# 21FX_revd_power.net
KiCad netlist of a schematic drawn in Altium Designer
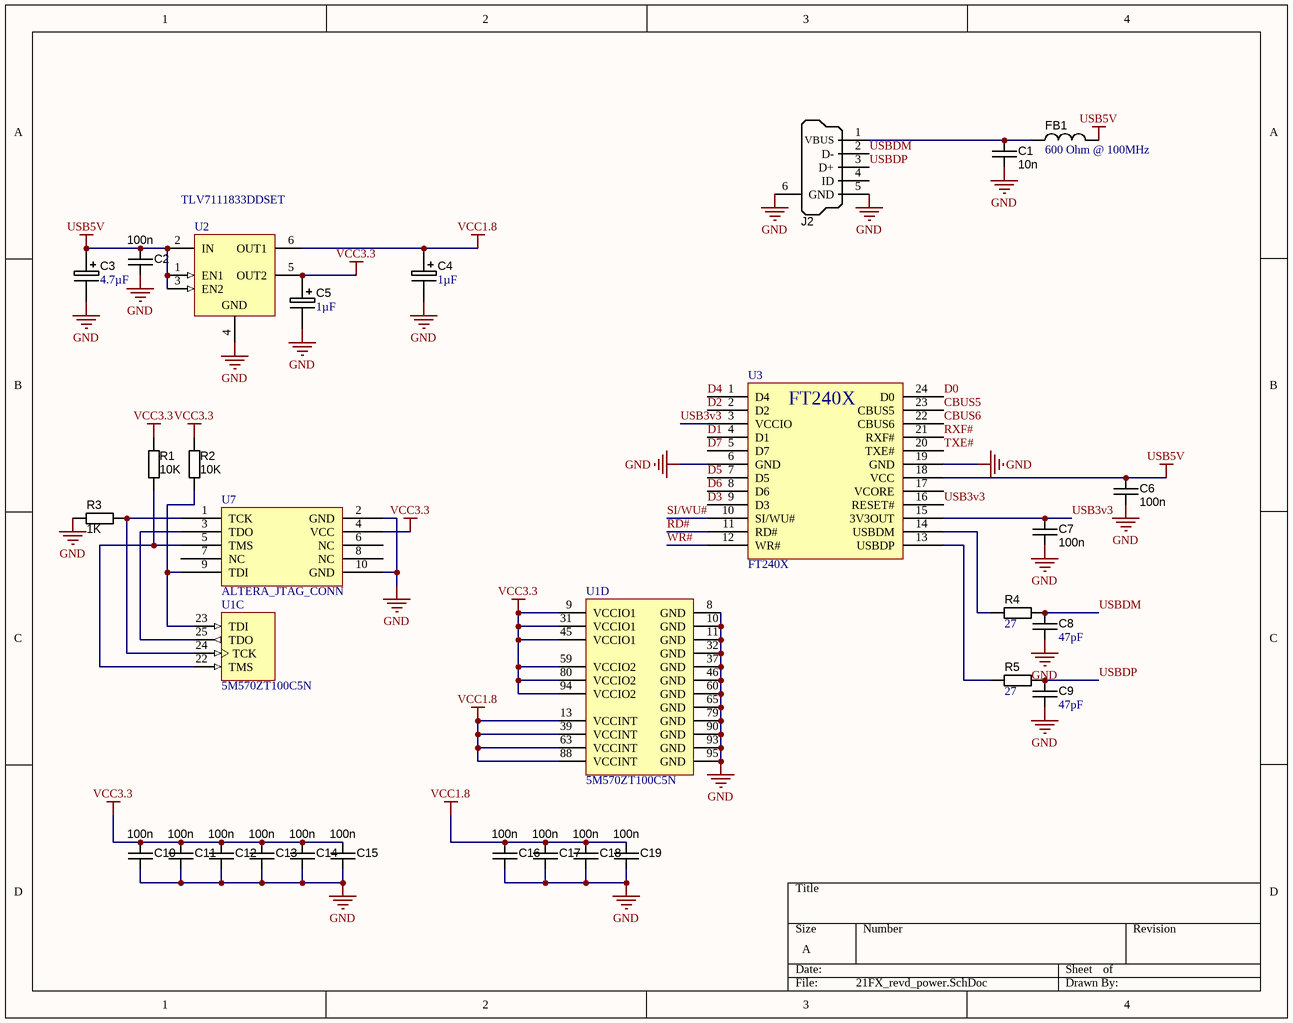
[diagram p0: 21FX_revd_power.SchDoc]

(export (version "E")
  (design (tool "Eeschema 10.0.6"))
  (components
    (comp (ref "C1")
      (value "10n")
      (footprint "CAPC1608X90N")
      (description "Capacitor SMD Cer 10nF 10% 50V X7R 0603")
      (fields (field (name "TOLERANCE") "±10%") (field (name "Comment") "approved sub OK"))
      (libsource (lib "snes_hook_parts") (part "CAPC_10n_0603_X7R_50V_10%"))
    )
    (comp (ref "C2")
      (value "100n")
      (footprint "CAPC1608X90N")
      (description "Capacitor SMD Cer 100nF 10% 50V X7R 0603")
      (fields (field (name "TOLERANCE") "±10%") (field (name "Comment") "approved sub OK"))
      (libsource (lib "snes_hook_parts") (part "CAPC_100n_0603_X7R_50V_10%"))
    )
    (comp (ref "C3")
      (value "~")
      (footprint "CAPC1608X90N")
      (description "Capacitor SMD 4.7uF 10% 10V")
      (fields
        (field (name "MANUFACTURER") "Yageo")
        (field (name "MANUFACTURER PART NUMBER") "CC0603KRX5R6BB475")
        (field (name "CAPACITANCE") "4.7µF")
      )
      (libsource (lib "snes_hook_parts") (part "CAPT_4_7u_0603_10V"))
    )
    (comp (ref "C4")
      (value "~")
      (footprint "CAPC1608X90N")
      (description "Capacitor SMD 1uF 10% 10V")
      (fields
        (field (name "MANUFACTURER") "Murata Electronics North America")
        (field (name "MANUFACTURER PART NUMBER") "GRM155R61A105KE15D")
        (field (name "CAPACITANCE") "1µF")
      )
      (libsource (lib "snes_hook_parts") (part "CAPT_1u_0603_10V"))
    )
    (comp (ref "C5")
      (value "~")
      (footprint "CAPC1608X90N")
      (description "Capacitor SMD 1uF 10% 10V")
      (fields
        (field (name "MANUFACTURER") "Murata Electronics North America")
        (field (name "MANUFACTURER PART NUMBER") "GRM155R61A105KE15D")
        (field (name "CAPACITANCE") "1µF")
      )
      (libsource (lib "snes_hook_parts") (part "CAPT_1u_0603_10V"))
    )
    (comp (ref "C6")
      (value "100n")
      (footprint "CAPC1608X90N")
      (description "Capacitor SMD Cer 100nF 10% 50V X7R 0603")
      (fields (field (name "TOLERANCE") "±10%") (field (name "Comment") "approved sub OK"))
      (libsource (lib "snes_hook_parts") (part "CAPC_100n_0603_X7R_50V_10%"))
    )
    (comp (ref "C7")
      (value "100n")
      (footprint "CAPC1608X90N")
      (description "Capacitor SMD Cer 100nF 10% 50V X7R 0603")
      (fields (field (name "TOLERANCE") "±10%") (field (name "Comment") "approved sub OK"))
      (libsource (lib "snes_hook_parts") (part "CAPC_100n_0603_X7R_50V_10%"))
    )
    (comp (ref "C8")
      (value "~")
      (footprint "CAPC1608X90N")
      (description "Capacitor SMD Cer 47pF 5% 50V X7R 0603")
      (fields (field (name "TOLERANCE") "±5%") (field (name "CAPACITANCE") "47pF"))
      (libsource (lib "snes_hook_parts") (part "CAPC_47p_0603_X7R_50V_5%"))
    )
    (comp (ref "C9")
      (value "~")
      (footprint "CAPC1608X90N")
      (description "Capacitor SMD Cer 47pF 5% 50V X7R 0603")
      (fields (field (name "TOLERANCE") "±5%") (field (name "CAPACITANCE") "47pF"))
      (libsource (lib "snes_hook_parts") (part "CAPC_47p_0603_X7R_50V_5%"))
    )
    (comp (ref "C10")
      (value "100n")
      (footprint "CAPC1608X90N")
      (description "Capacitor SMD Cer 100nF 10% 50V X7R 0603")
      (fields (field (name "TOLERANCE") "±10%") (field (name "Comment") "approved sub OK"))
      (libsource (lib "snes_hook_parts") (part "CAPC_100n_0603_X7R_50V_10%"))
    )
    (comp (ref "C11")
      (value "100n")
      (footprint "CAPC1608X90N")
      (description "Capacitor SMD Cer 100nF 10% 50V X7R 0603")
      (fields (field (name "TOLERANCE") "±10%") (field (name "Comment") "approved sub OK"))
      (libsource (lib "snes_hook_parts") (part "CAPC_100n_0603_X7R_50V_10%"))
    )
    (comp (ref "C12")
      (value "100n")
      (footprint "CAPC1608X90N")
      (description "Capacitor SMD Cer 100nF 10% 50V X7R 0603")
      (fields (field (name "TOLERANCE") "±10%") (field (name "Comment") "approved sub OK"))
      (libsource (lib "snes_hook_parts") (part "CAPC_100n_0603_X7R_50V_10%"))
    )
    (comp (ref "C13")
      (value "100n")
      (footprint "CAPC1608X90N")
      (description "Capacitor SMD Cer 100nF 10% 50V X7R 0603")
      (fields (field (name "TOLERANCE") "±10%") (field (name "Comment") "approved sub OK"))
      (libsource (lib "snes_hook_parts") (part "CAPC_100n_0603_X7R_50V_10%"))
    )
    (comp (ref "C14")
      (value "100n")
      (footprint "CAPC1608X90N")
      (description "Capacitor SMD Cer 100nF 10% 50V X7R 0603")
      (fields (field (name "TOLERANCE") "±10%") (field (name "Comment") "approved sub OK"))
      (libsource (lib "snes_hook_parts") (part "CAPC_100n_0603_X7R_50V_10%"))
    )
    (comp (ref "C15")
      (value "100n")
      (footprint "CAPC1608X90N")
      (description "Capacitor SMD Cer 100nF 10% 50V X7R 0603")
      (fields (field (name "TOLERANCE") "±10%") (field (name "Comment") "approved sub OK"))
      (libsource (lib "snes_hook_parts") (part "CAPC_100n_0603_X7R_50V_10%"))
    )
    (comp (ref "C16")
      (value "100n")
      (footprint "CAPC1608X90N")
      (description "Capacitor SMD Cer 100nF 10% 50V X7R 0603")
      (fields (field (name "TOLERANCE") "±10%") (field (name "Comment") "approved sub OK"))
      (libsource (lib "snes_hook_parts") (part "CAPC_100n_0603_X7R_50V_10%"))
    )
    (comp (ref "C17")
      (value "100n")
      (footprint "CAPC1608X90N")
      (description "Capacitor SMD Cer 100nF 10% 50V X7R 0603")
      (fields (field (name "TOLERANCE") "±10%") (field (name "Comment") "approved sub OK"))
      (libsource (lib "snes_hook_parts") (part "CAPC_100n_0603_X7R_50V_10%"))
    )
    (comp (ref "C18")
      (value "100n")
      (footprint "CAPC1608X90N")
      (description "Capacitor SMD Cer 100nF 10% 50V X7R 0603")
      (fields (field (name "TOLERANCE") "±10%") (field (name "Comment") "approved sub OK"))
      (libsource (lib "snes_hook_parts") (part "CAPC_100n_0603_X7R_50V_10%"))
    )
    (comp (ref "C19")
      (value "100n")
      (footprint "CAPC1608X90N")
      (description "Capacitor SMD Cer 100nF 10% 50V X7R 0603")
      (fields (field (name "TOLERANCE") "±10%") (field (name "Comment") "approved sub OK"))
      (libsource (lib "snes_hook_parts") (part "CAPC_100n_0603_X7R_50V_10%"))
    )
    (comp (ref "FB1")
      (value "~")
      (footprint "FBC2012N")
      (description "Ferrite bead 600 Ohm at 100 MHz 1.5A 0805 SMD")
      (fields (field (name "IMPEDANCE @ FREQUENCY") "600 Ohm @ 100MHz"))
      (libsource (lib "snes_hook_parts") (part "FERRITE_600-100MHz_0805"))
    )
    (comp (ref "J2")
      (value "USB_Mini-B_TH")
      (footprint "USB_MINI-B_WURTH-TH")
      (description "Connector TH USB Type Mini-B")
      (fields
        (field (name "MANUFACTURER") "Wurth Electronics Inc")
        (field (name "MANUFACTURER PART NUMBER") "651005136521")
      )
      (libsource (lib "snes_hook_parts") (part "USB_Mini-B_TH"))
    )
    (comp (ref "R1")
      (value "10K")
      (footprint "RESC1608X55N")
      (description "Resistor SMD chip 10k Ohm 0.1W 5% 0603")
      (fields (field (name "TOLERANCE") "±5%") (field (name "Comment") "Thick Film"))
      (libsource (lib "snes_hook_parts") (part "RES_10K_0603_5%"))
    )
    (comp (ref "R2")
      (value "10K")
      (footprint "RESC1608X55N")
      (description "Resistor SMD chip 10k Ohm 0.1W 5% 0603")
      (fields (field (name "TOLERANCE") "±5%") (field (name "Comment") "Thick Film"))
      (libsource (lib "snes_hook_parts") (part "RES_10K_0603_5%"))
    )
    (comp (ref "R3")
      (value "1K")
      (footprint "RESC1608X55N")
      (description "Resistor SMD chip 1k Ohm 0.1W 5% 0603")
      (fields (field (name "TOLERANCE") "±5%") (field (name "Comment") "Thick Film"))
      (libsource (lib "snes_hook_parts") (part "RES_1K_0603_5%"))
    )
    (comp (ref "R4")
      (value "Thick Film")
      (footprint "RESC1608X55N")
      (description "Resistor SMD chip 27 Ohm 0.1W 5% 0603")
      (fields (field (name "TOLERANCE") "±5%") (field (name "RESISTANCE (OHMS)") "27"))
      (libsource (lib "snes_hook_parts") (part "RES_27R_0603_5%"))
    )
    (comp (ref "R5")
      (value "Thick Film")
      (footprint "RESC1608X55N")
      (description "Resistor SMD chip 27 Ohm 0.1W 5% 0603")
      (fields (field (name "TOLERANCE") "±5%") (field (name "RESISTANCE (OHMS)") "27"))
      (libsource (lib "snes_hook_parts") (part "RES_27R_0603_5%"))
    )
    (comp (ref "U1")
      (value "5M570ZT100C5N")
      (footprint "TQFP100_A-120_N")
      (libsource (lib "snes_hook_parts") (part "5M570ZT100C5N"))
    )
    (comp (ref "U2")
      (value "TLV7111833DDSET")
      (footprint "TI-DSE6_V")
      (fields (field (name "MANUFACTURER") "Texas Instruments"))
      (libsource (lib "TI Power Management Linear Regulator Dual Channel LDO") (part "TLV7111833DDSET"))
    )
    (comp (ref "U3")
      (value "FT240X")
      (footprint "SSOP-24")
      (libsource (lib "snes_hook_parts") (part "FT240X"))
    )
    (comp (ref "U7")
      (value "ALTERA_JTAG_CONN")
      (footprint "JTAG_CONN")
      (libsource (lib "snes_hook_parts") (part "ALTERA_JTAG_CONN"))
    )
  )
  (nets
    (net (code "1") (name "/CBUS5") (class "Default")
      (node (ref "U3") (pin "23") (pinfunction "CBUS5_23") (pintype "passive"))
    )
    (net (code "2") (name "/CBUS6") (class "Default")
      (node (ref "U3") (pin "22") (pinfunction "CBUS6_22") (pintype "passive"))
    )
    (net (code "3") (name "/D0") (class "Default")
      (node (ref "U3") (pin "24") (pinfunction "D0_24") (pintype "passive"))
    )
    (net (code "4") (name "/D1") (class "Default")
      (node (ref "U3") (pin "4") (pinfunction "D1_4") (pintype "passive"))
    )
    (net (code "5") (name "/D2") (class "Default")
      (node (ref "U3") (pin "2") (pinfunction "D2_2") (pintype "passive"))
    )
    (net (code "6") (name "/D3") (class "Default")
      (node (ref "U3") (pin "9") (pinfunction "D3_9") (pintype "passive"))
    )
    (net (code "7") (name "/D4") (class "Default")
      (node (ref "U3") (pin "1") (pinfunction "D4_1") (pintype "passive"))
    )
    (net (code "8") (name "/D5") (class "Default")
      (node (ref "U3") (pin "7") (pinfunction "D5_7") (pintype "passive"))
    )
    (net (code "9") (name "/D6") (class "Default")
      (node (ref "U3") (pin "8") (pinfunction "D6_8") (pintype "passive"))
    )
    (net (code "10") (name "/D7") (class "Default")
      (node (ref "U3") (pin "5") (pinfunction "D7_5") (pintype "passive"))
    )
    (net (code "11") (name "/RD#") (class "Default")
      (node (ref "U3") (pin "11") (pinfunction "RD#_11") (pintype "passive"))
    )
    (net (code "12") (name "/RXF#") (class "Default")
      (node (ref "U3") (pin "21") (pinfunction "RXF#_21") (pintype "passive"))
    )
    (net (code "13") (name "/SI{slash}WU#") (class "Default")
      (node (ref "U3") (pin "10") (pinfunction "SI/WU#_10") (pintype "passive"))
    )
    (net (code "14") (name "/TXE#") (class "Default")
      (node (ref "U3") (pin "20") (pinfunction "TXE#_20") (pintype "passive"))
    )
    (net (code "15") (name "/USB3v3") (class "Default")
      (node (ref "C7") (pin "1") (pintype "passive"))
      (node (ref "U3") (pin "15") (pinfunction "3V3OUT_15") (pintype "passive"))
      (node (ref "U3") (pin "16") (pinfunction "RESET#_16") (pintype "passive"))
      (node (ref "U3") (pin "3") (pinfunction "VCCIO_3") (pintype "passive"))
    )
    (net (code "16") (name "/USBDM") (class "Default")
      (node (ref "C8") (pin "1") (pintype "passive"))
      (node (ref "J2") (pin "2") (pinfunction "D-_2") (pintype "passive"))
      (node (ref "R4") (pin "2") (pinfunction "2_2") (pintype "passive"))
    )
    (net (code "17") (name "/USBDP") (class "Default")
      (node (ref "C9") (pin "1") (pintype "passive"))
      (node (ref "J2") (pin "3") (pinfunction "D+_3") (pintype "passive"))
      (node (ref "R5") (pin "2") (pinfunction "2_2") (pintype "passive"))
    )
    (net (code "18") (name "/WR#") (class "Default")
      (node (ref "U3") (pin "12") (pinfunction "WR#_12") (pintype "passive"))
    )
    (net (code "19") (name "GND") (class "Default")
      (node (ref "C1") (pin "2") (pintype "passive"))
      (node (ref "C10") (pin "2") (pintype "passive"))
      (node (ref "C11") (pin "2") (pintype "passive"))
      (node (ref "C12") (pin "2") (pintype "passive"))
      (node (ref "C13") (pin "2") (pintype "passive"))
      (node (ref "C14") (pin "2") (pintype "passive"))
      (node (ref "C15") (pin "2") (pintype "passive"))
      (node (ref "C16") (pin "2") (pintype "passive"))
      (node (ref "C17") (pin "2") (pintype "passive"))
      (node (ref "C18") (pin "2") (pintype "passive"))
      (node (ref "C19") (pin "2") (pintype "passive"))
      (node (ref "C2") (pin "2") (pintype "passive"))
      (node (ref "C3") (pin "2") (pintype "passive"))
      (node (ref "C4") (pin "2") (pintype "passive"))
      (node (ref "C5") (pin "2") (pintype "passive"))
      (node (ref "C6") (pin "2") (pintype "passive"))
      (node (ref "C7") (pin "2") (pintype "passive"))
      (node (ref "C8") (pin "2") (pintype "passive"))
      (node (ref "C9") (pin "2") (pintype "passive"))
      (node (ref "J2") (pin "5") (pinfunction "GND_5") (pintype "passive"))
      (node (ref "J2") (pin "6") (pinfunction "Shell_6") (pintype "passive"))
      (node (ref "R3") (pin "1") (pinfunction "1_1") (pintype "passive"))
      (node (ref "U1") (pin "10") (pinfunction "GND_10") (pintype "power_in"))
      (node (ref "U1") (pin "11") (pinfunction "GND_11") (pintype "power_in"))
      (node (ref "U1") (pin "32") (pinfunction "GND_32") (pintype "power_in"))
      (node (ref "U1") (pin "37") (pinfunction "GND_37") (pintype "power_in"))
      (node (ref "U1") (pin "46") (pinfunction "GND_46") (pintype "power_in"))
      (node (ref "U1") (pin "60") (pinfunction "GND_60") (pintype "power_in"))
      (node (ref "U1") (pin "65") (pinfunction "GND_65") (pintype "power_in"))
      (node (ref "U1") (pin "79") (pinfunction "GND_79") (pintype "power_in"))
      (node (ref "U1") (pin "8") (pinfunction "GND_8") (pintype "power_in"))
      (node (ref "U1") (pin "90") (pinfunction "GND_90") (pintype "power_in"))
      (node (ref "U1") (pin "93") (pinfunction "GND_93") (pintype "power_in"))
      (node (ref "U1") (pin "95") (pinfunction "GND_95") (pintype "power_in"))
      (node (ref "U2") (pin "4") (pinfunction "GND_4") (pintype "power_in"))
      (node (ref "U3") (pin "19") (pinfunction "GND_19") (pintype "passive"))
      (node (ref "U3") (pin "6") (pinfunction "GND_6") (pintype "passive"))
      (node (ref "U7") (pin "10") (pinfunction "GND_10") (pintype "passive"))
      (node (ref "U7") (pin "2") (pinfunction "GND_2") (pintype "passive"))
    )
    (net (code "20") (name "Net-(J2-VBUS)") (class "Default")
      (node (ref "C1") (pin "1") (pintype "passive"))
      (node (ref "FB1") (pin "1") (pinfunction "1_1") (pintype "passive"))
      (node (ref "J2") (pin "1") (pinfunction "VBUS_1") (pintype "passive"))
    )
    (net (code "21") (name "Net-(U1C-TCK)") (class "Default")
      (node (ref "R3") (pin "2") (pinfunction "2_2") (pintype "passive"))
      (node (ref "U1") (pin "24") (pinfunction "TCK_24") (pintype "input"))
      (node (ref "U7") (pin "1") (pinfunction "TCK_1") (pintype "passive"))
    )
    (net (code "22") (name "Net-(U1C-TDI)") (class "Default")
      (node (ref "R2") (pin "2") (pinfunction "2_2") (pintype "passive"))
      (node (ref "U1") (pin "23") (pinfunction "TDI_23") (pintype "input"))
      (node (ref "U7") (pin "9") (pinfunction "TDI_9") (pintype "passive"))
    )
    (net (code "23") (name "Net-(U1C-TDO)") (class "Default")
      (node (ref "U1") (pin "25") (pinfunction "TDO_25") (pintype "output"))
      (node (ref "U7") (pin "3") (pinfunction "TDO_3") (pintype "passive"))
    )
    (net (code "24") (name "Net-(U1C-TMS)") (class "Default")
      (node (ref "R1") (pin "2") (pinfunction "2_2") (pintype "passive"))
      (node (ref "U1") (pin "22") (pinfunction "TMS_22") (pintype "input"))
      (node (ref "U7") (pin "5") (pinfunction "TMS_5") (pintype "passive"))
    )
    (net (code "25") (name "Net-(U3-USBDM)") (class "Default")
      (node (ref "R4") (pin "1") (pinfunction "1_1") (pintype "passive"))
      (node (ref "U3") (pin "14") (pinfunction "USBDM_14") (pintype "passive"))
    )
    (net (code "26") (name "Net-(U3-USBDP)") (class "Default")
      (node (ref "R5") (pin "1") (pinfunction "1_1") (pintype "passive"))
      (node (ref "U3") (pin "13") (pinfunction "USBDP_13") (pintype "passive"))
    )
    (net (code "27") (name "USB5V") (class "Default")
      (node (ref "C2") (pin "1") (pintype "passive"))
      (node (ref "C3") (pin "1") (pintype "passive"))
      (node (ref "C6") (pin "1") (pintype "passive"))
      (node (ref "FB1") (pin "2") (pinfunction "2_2") (pintype "passive"))
      (node (ref "U2") (pin "1") (pinfunction "EN1_1") (pintype "input"))
      (node (ref "U2") (pin "2") (pinfunction "IN_2") (pintype "power_in"))
      (node (ref "U2") (pin "3") (pinfunction "EN2_3") (pintype "input"))
      (node (ref "U3") (pin "18") (pinfunction "VCC_18") (pintype "passive"))
    )
    (net (code "28") (name "VCC1.8") (class "Default")
      (node (ref "C16") (pin "1") (pintype "passive"))
      (node (ref "C17") (pin "1") (pintype "passive"))
      (node (ref "C18") (pin "1") (pintype "passive"))
      (node (ref "C19") (pin "1") (pintype "passive"))
      (node (ref "C4") (pin "1") (pintype "passive"))
      (node (ref "U1") (pin "13") (pinfunction "VCCINT_13") (pintype "power_in"))
      (node (ref "U1") (pin "39") (pinfunction "VCCINT_39") (pintype "power_in"))
      (node (ref "U1") (pin "63") (pinfunction "VCCINT_63") (pintype "power_in"))
      (node (ref "U1") (pin "88") (pinfunction "VCCINT_88") (pintype "power_in"))
      (node (ref "U2") (pin "6") (pinfunction "OUT1_6") (pintype "power_in"))
    )
    (net (code "29") (name "VCC3.3") (class "Default")
      (node (ref "C10") (pin "1") (pintype "passive"))
      (node (ref "C11") (pin "1") (pintype "passive"))
      (node (ref "C12") (pin "1") (pintype "passive"))
      (node (ref "C13") (pin "1") (pintype "passive"))
      (node (ref "C14") (pin "1") (pintype "passive"))
      (node (ref "C15") (pin "1") (pintype "passive"))
      (node (ref "C5") (pin "1") (pintype "passive"))
      (node (ref "R1") (pin "1") (pinfunction "1_1") (pintype "passive"))
      (node (ref "R2") (pin "1") (pinfunction "1_1") (pintype "passive"))
      (node (ref "U1") (pin "31") (pinfunction "VCCIO1_31") (pintype "power_in"))
      (node (ref "U1") (pin "45") (pinfunction "VCCIO1_45") (pintype "power_in"))
      (node (ref "U1") (pin "59") (pinfunction "VCCIO2_59") (pintype "power_in"))
      (node (ref "U1") (pin "80") (pinfunction "VCCIO2_80") (pintype "power_in"))
      (node (ref "U1") (pin "9") (pinfunction "VCCIO1_9") (pintype "power_in"))
      (node (ref "U1") (pin "94") (pinfunction "VCCIO2_94") (pintype "power_in"))
      (node (ref "U2") (pin "5") (pinfunction "OUT2_5") (pintype "power_in"))
      (node (ref "U7") (pin "4") (pinfunction "VCC_4") (pintype "passive"))
    )
    (net (code "30") (name "unconnected-(J2-ID-Pad4)") (class "Default")
      (node (ref "J2") (pin "4") (pinfunction "ID_4") (pintype "passive"))
    )
    (net (code "31") (name "unconnected-(U3-VCORE-Pad17)") (class "Default")
      (node (ref "U3") (pin "17") (pinfunction "VCORE_17") (pintype "passive"))
    )
    (net (code "32") (name "unconnected-(U7-NC-Pad6)") (class "Default")
      (node (ref "U7") (pin "6") (pinfunction "NC_6") (pintype "passive"))
    )
    (net (code "33") (name "unconnected-(U7-NC-Pad7)") (class "Default")
      (node (ref "U7") (pin "7") (pinfunction "NC_7") (pintype "passive"))
    )
    (net (code "34") (name "unconnected-(U7-NC-Pad8)") (class "Default")
      (node (ref "U7") (pin "8") (pinfunction "NC_8") (pintype "passive"))
    )
  )
)
